# ds3231.net
KiCad netlist of a schematic drawn in Altium Designer
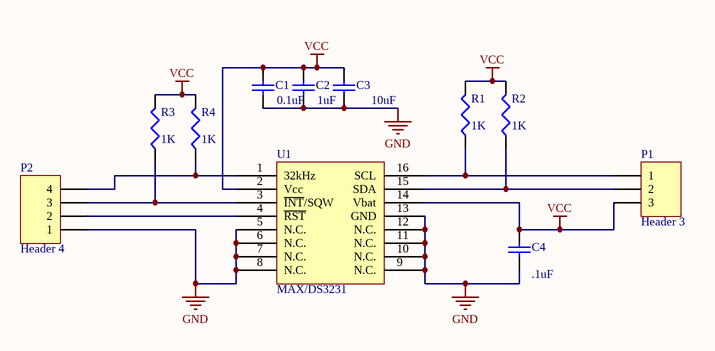
[diagram p0: ds3231.SchDoc]

(export (version "E")
  (design (tool "Eeschema 10.0.6"))
  (components
    (comp (ref "C1")
      (value "0.1uF")
      (footprint "CC1608-0603")
      (description "Capacitor")
      (fields (field (name "Comment") "Cap") (field (name "PUBLISHER") "Altium Limited"))
      (libsource (lib "Miscellaneous Devices") (part "Cap"))
    )
    (comp (ref "C2")
      (value "1uF")
      (footprint "CC1608-0603")
      (description "Capacitor")
      (fields (field (name "Comment") "Cap") (field (name "PUBLISHER") "Altium Limited"))
      (libsource (lib "Miscellaneous Devices") (part "Cap"))
    )
    (comp (ref "C3")
      (value "10uF")
      (footprint "CC1608-0603")
      (description "Capacitor")
      (fields (field (name "Comment") "Cap") (field (name "PUBLISHER") "Altium Limited"))
      (libsource (lib "Miscellaneous Devices") (part "Cap"))
    )
    (comp (ref "C4")
      (value ".1uF")
      (footprint "CC1608-0603")
      (description "Capacitor")
      (fields (field (name "Comment") "Cap") (field (name "PUBLISHER") "Altium Limited"))
      (libsource (lib "Miscellaneous Devices") (part "Cap"))
    )
    (comp (ref "P1")
      (value "Header 3")
      (footprint "HDR1X3")
      (description "Header, 3-Pin")
      (fields (field (name "PUBLISHER") "Altium Limited"))
      (libsource (lib "Miscellaneous Connectors") (part "Header 3"))
    )
    (comp (ref "P2")
      (value "Header 4")
      (footprint "HDR1X4")
      (description "Header, 4-Pin")
      (fields (field (name "PUBLISHER") "Altium Limited"))
      (libsource (lib "Miscellaneous Connectors") (part "Header 4"))
    )
    (comp (ref "R1")
      (value "1K")
      (footprint "CR1608-0603")
      (description "Resistor")
      (fields (field (name "Comment") "Res3") (field (name "PUBLISHER") "Altium Limited"))
      (libsource (lib "Miscellaneous Devices") (part "Res3"))
    )
    (comp (ref "R2")
      (value "1K")
      (footprint "CR1608-0603")
      (description "Resistor")
      (fields (field (name "Comment") "Res3") (field (name "PUBLISHER") "Altium Limited"))
      (libsource (lib "Miscellaneous Devices") (part "Res3"))
    )
    (comp (ref "R3")
      (value "1K")
      (footprint "CR1608-0603")
      (description "Resistor")
      (fields (field (name "Comment") "Res3") (field (name "PUBLISHER") "Altium Limited"))
      (libsource (lib "Miscellaneous Devices") (part "Res3"))
    )
    (comp (ref "R4")
      (value "1K")
      (footprint "CR1608-0603")
      (description "Resistor")
      (fields (field (name "Comment") "Res3") (field (name "PUBLISHER") "Altium Limited"))
      (libsource (lib "Miscellaneous Devices") (part "Res3"))
    )
    (comp (ref "U1")
      (value "MAX/DS3231")
      (footprint "SOIC16 - DS3231")
      (description "MAX DS3231")
      (libsource (lib "thomas_ds3231") (part "MAX/DS3231"))
    )
  )
  (nets
    (net (code "1") (name "GND") (class "Default")
      (node (ref "C1") (pin "1") (pinfunction "1_1") (pintype "passive"))
      (node (ref "C2") (pin "1") (pinfunction "1_1") (pintype "passive"))
      (node (ref "C3") (pin "1") (pinfunction "1_1") (pintype "passive"))
      (node (ref "C4") (pin "1") (pinfunction "1_1") (pintype "passive"))
      (node (ref "P2") (pin "1") (pinfunction "1_1") (pintype "passive"))
      (node (ref "U1") (pin "10") (pinfunction "N.C._10") (pintype "passive"))
      (node (ref "U1") (pin "11") (pinfunction "N.C._11") (pintype "passive"))
      (node (ref "U1") (pin "12") (pinfunction "N.C._12") (pintype "passive"))
      (node (ref "U1") (pin "13") (pinfunction "GND_13") (pintype "passive"))
      (node (ref "U1") (pin "5") (pinfunction "N.C._5") (pintype "passive"))
      (node (ref "U1") (pin "6") (pinfunction "N.C._6") (pintype "passive"))
      (node (ref "U1") (pin "7") (pinfunction "N.C._7") (pintype "passive"))
      (node (ref "U1") (pin "8") (pinfunction "N.C._8") (pintype "passive"))
      (node (ref "U1") (pin "9") (pinfunction "N.C._9") (pintype "passive"))
    )
    (net (code "2") (name "Net-(U1-32kHz)") (class "Default")
      (node (ref "P2") (pin "4") (pinfunction "4_4") (pintype "passive"))
      (node (ref "R4") (pin "1") (pinfunction "1_1") (pintype "passive"))
      (node (ref "U1") (pin "1") (pinfunction "32kHz_1") (pintype "passive"))
    )
    (net (code "3") (name "Net-(U1-SCL)") (class "Default")
      (node (ref "P1") (pin "1") (pinfunction "1_1") (pintype "passive"))
      (node (ref "R1") (pin "1") (pinfunction "1_1") (pintype "passive"))
      (node (ref "U1") (pin "16") (pinfunction "SCL_16") (pintype "passive"))
    )
    (net (code "4") (name "Net-(U1-SDA)") (class "Default")
      (node (ref "P1") (pin "2") (pinfunction "2_2") (pintype "passive"))
      (node (ref "R2") (pin "1") (pinfunction "1_1") (pintype "passive"))
      (node (ref "U1") (pin "15") (pinfunction "SDA_15") (pintype "passive"))
    )
    (net (code "5") (name "Net-(U1-~{INT}{slash}SQW)") (class "Default")
      (node (ref "P2") (pin "3") (pinfunction "3_3") (pintype "passive"))
      (node (ref "R3") (pin "1") (pinfunction "1_1") (pintype "passive"))
      (node (ref "U1") (pin "3") (pinfunction "~{INT}/SQW_3") (pintype "passive"))
    )
    (net (code "6") (name "Net-(U1-~{RST})") (class "Default")
      (node (ref "P2") (pin "2") (pinfunction "2_2") (pintype "passive"))
      (node (ref "U1") (pin "4") (pinfunction "~{RST}_4") (pintype "passive"))
    )
    (net (code "7") (name "VCC") (class "Default")
      (node (ref "C1") (pin "2") (pinfunction "2_2") (pintype "passive"))
      (node (ref "C2") (pin "2") (pinfunction "2_2") (pintype "passive"))
      (node (ref "C3") (pin "2") (pinfunction "2_2") (pintype "passive"))
      (node (ref "C4") (pin "2") (pinfunction "2_2") (pintype "passive"))
      (node (ref "P1") (pin "3") (pinfunction "3_3") (pintype "passive"))
      (node (ref "R1") (pin "2") (pinfunction "2_2") (pintype "passive"))
      (node (ref "R2") (pin "2") (pinfunction "2_2") (pintype "passive"))
      (node (ref "R3") (pin "2") (pinfunction "2_2") (pintype "passive"))
      (node (ref "R4") (pin "2") (pinfunction "2_2") (pintype "passive"))
      (node (ref "U1") (pin "14") (pinfunction "Vbat_14") (pintype "passive"))
      (node (ref "U1") (pin "2") (pinfunction "Vcc_2") (pintype "passive"))
    )
  )
)
